# 3_DO.net
KiCad netlist of a schematic drawn in Altium Designer
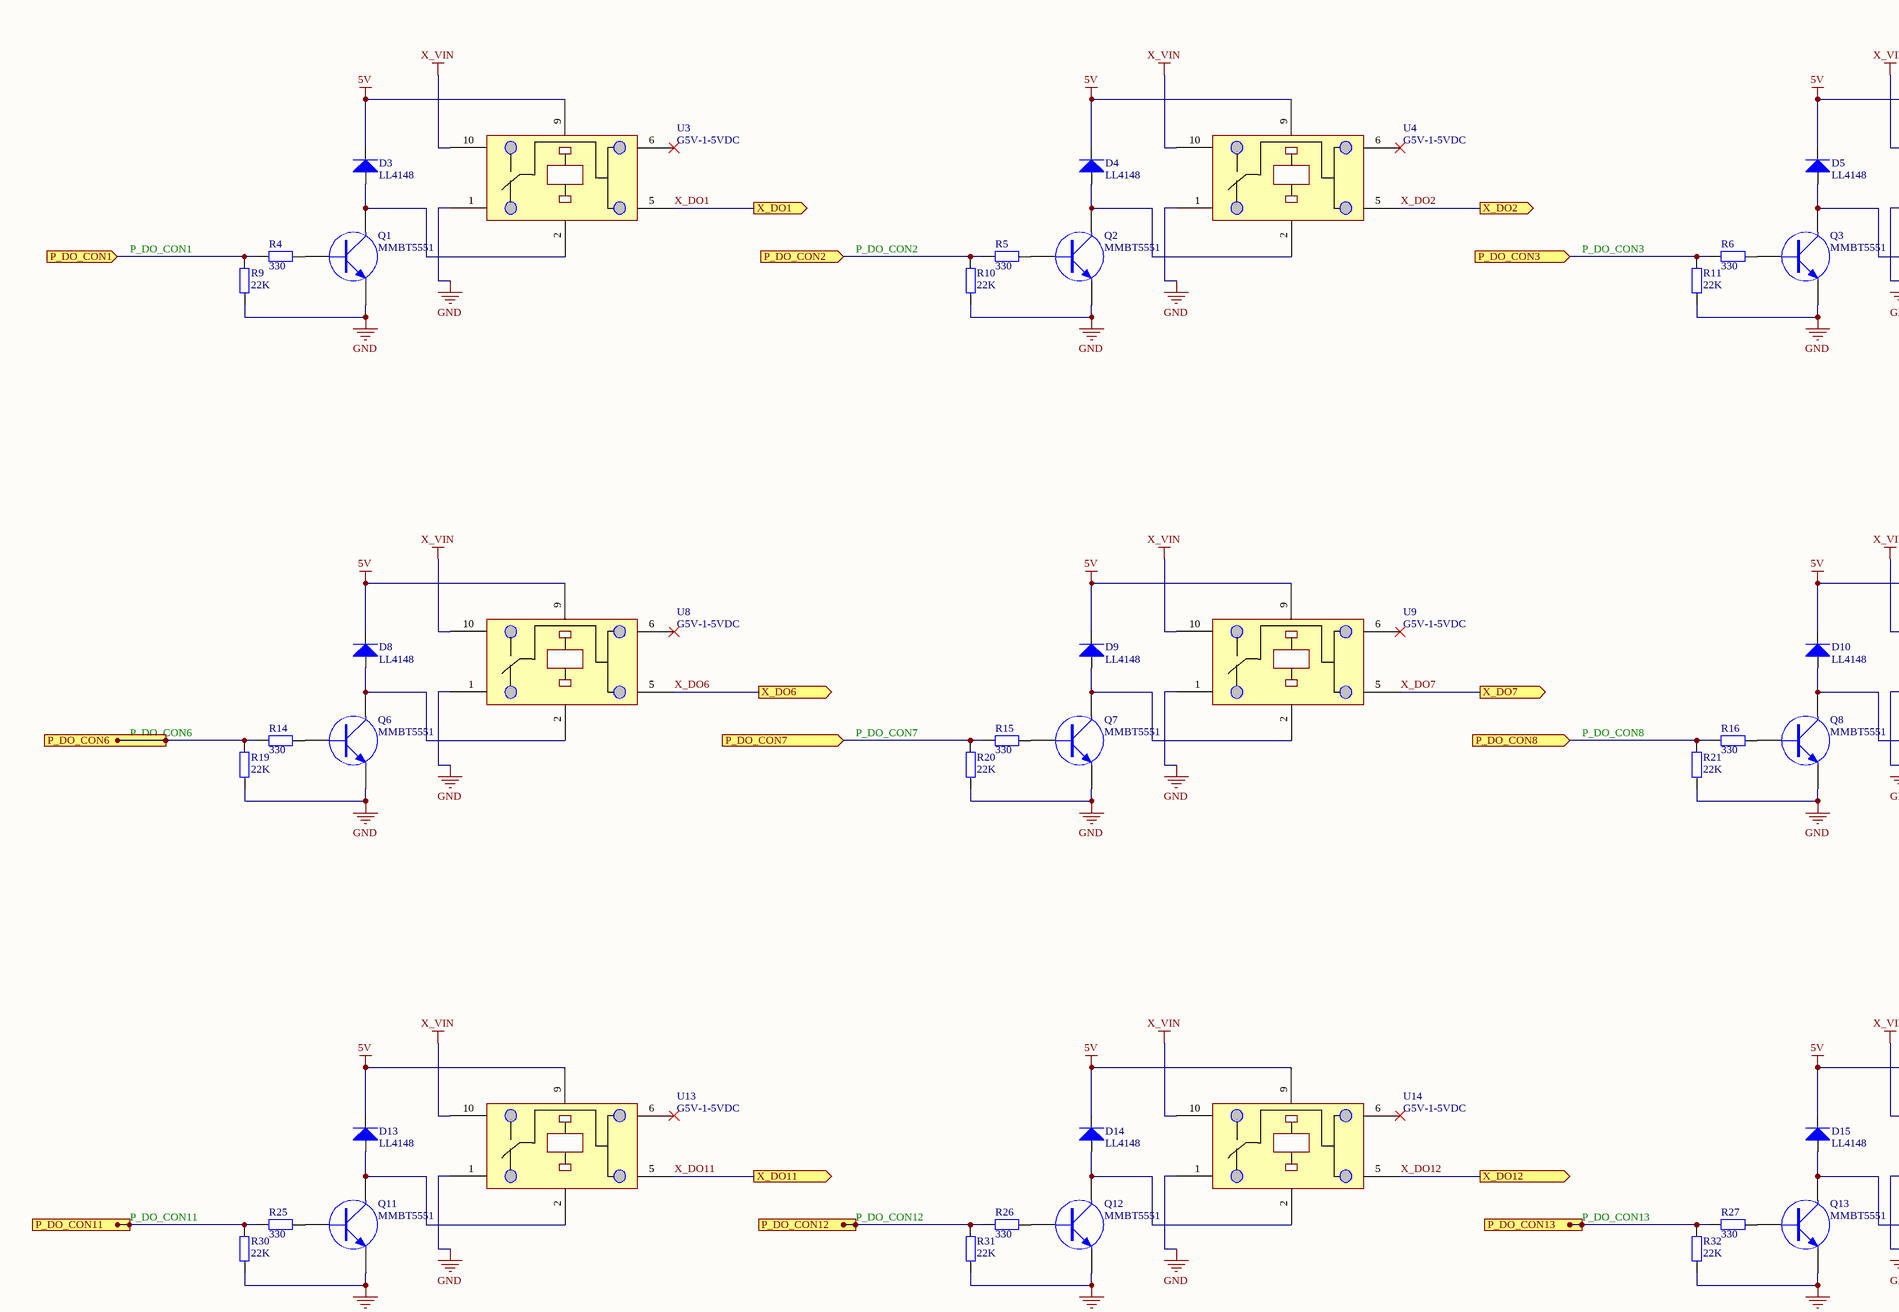
[diagram p0: 3.DO.SchDoc, top left]
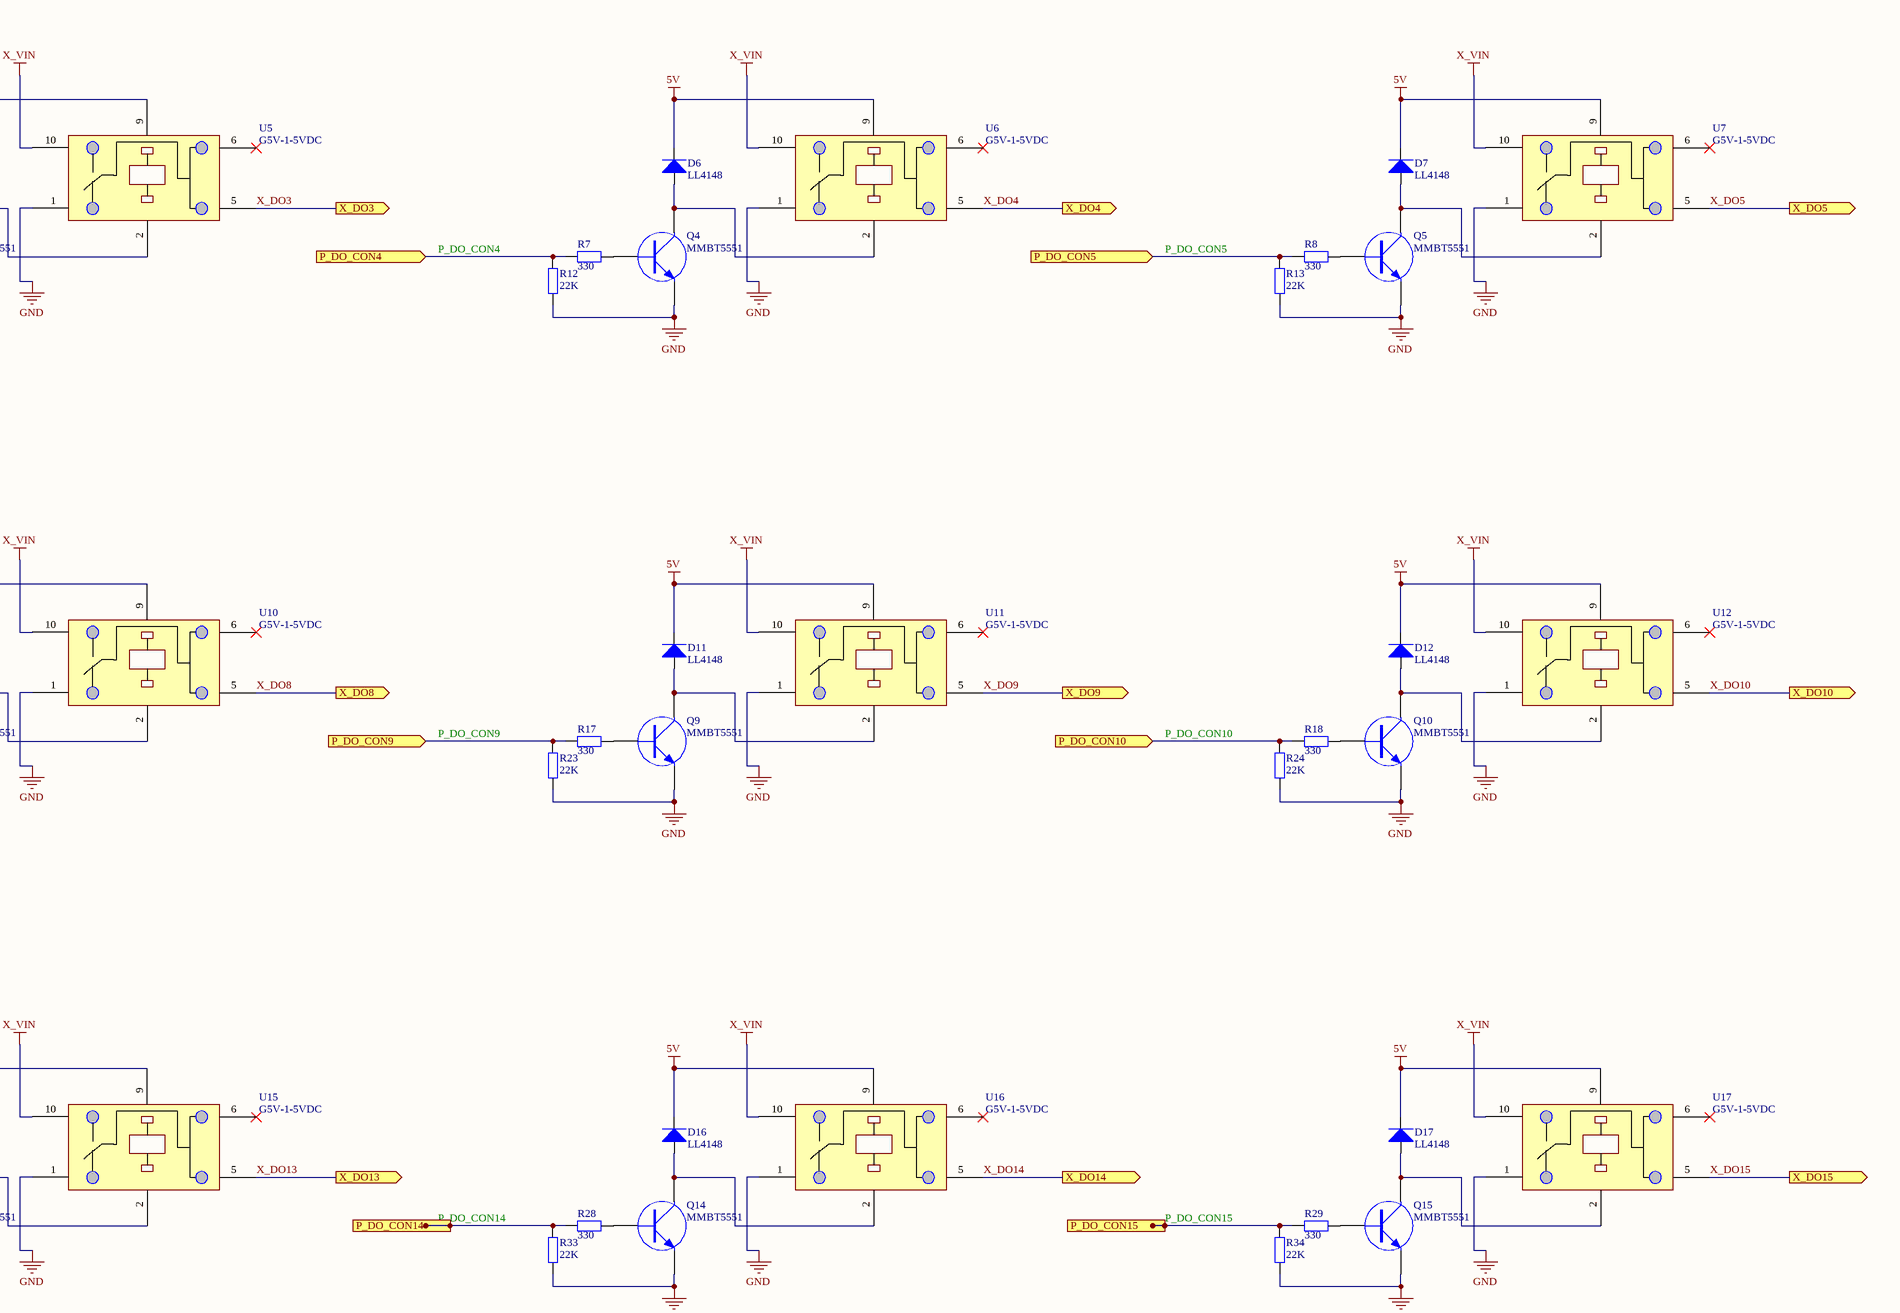
[diagram p1: 3.DO.SchDoc, top right]
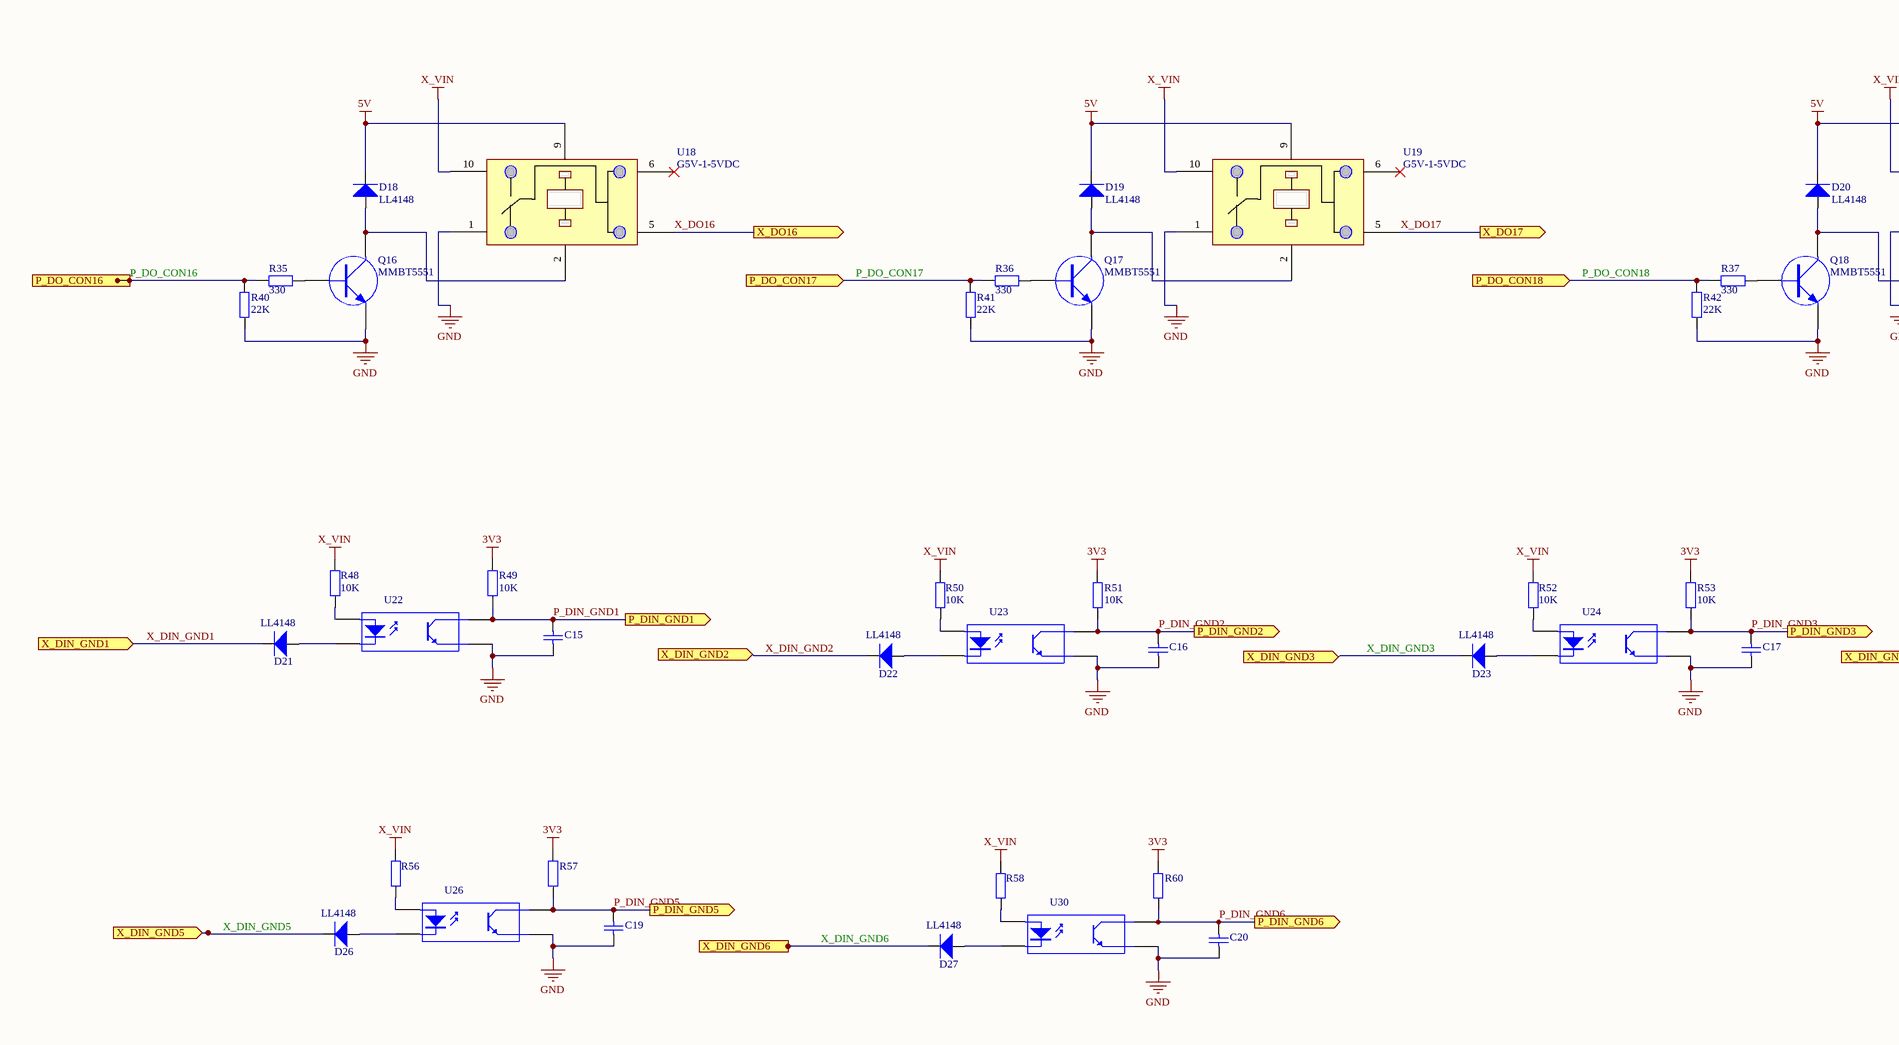
[diagram p2: 3.DO.SchDoc, bottom left]
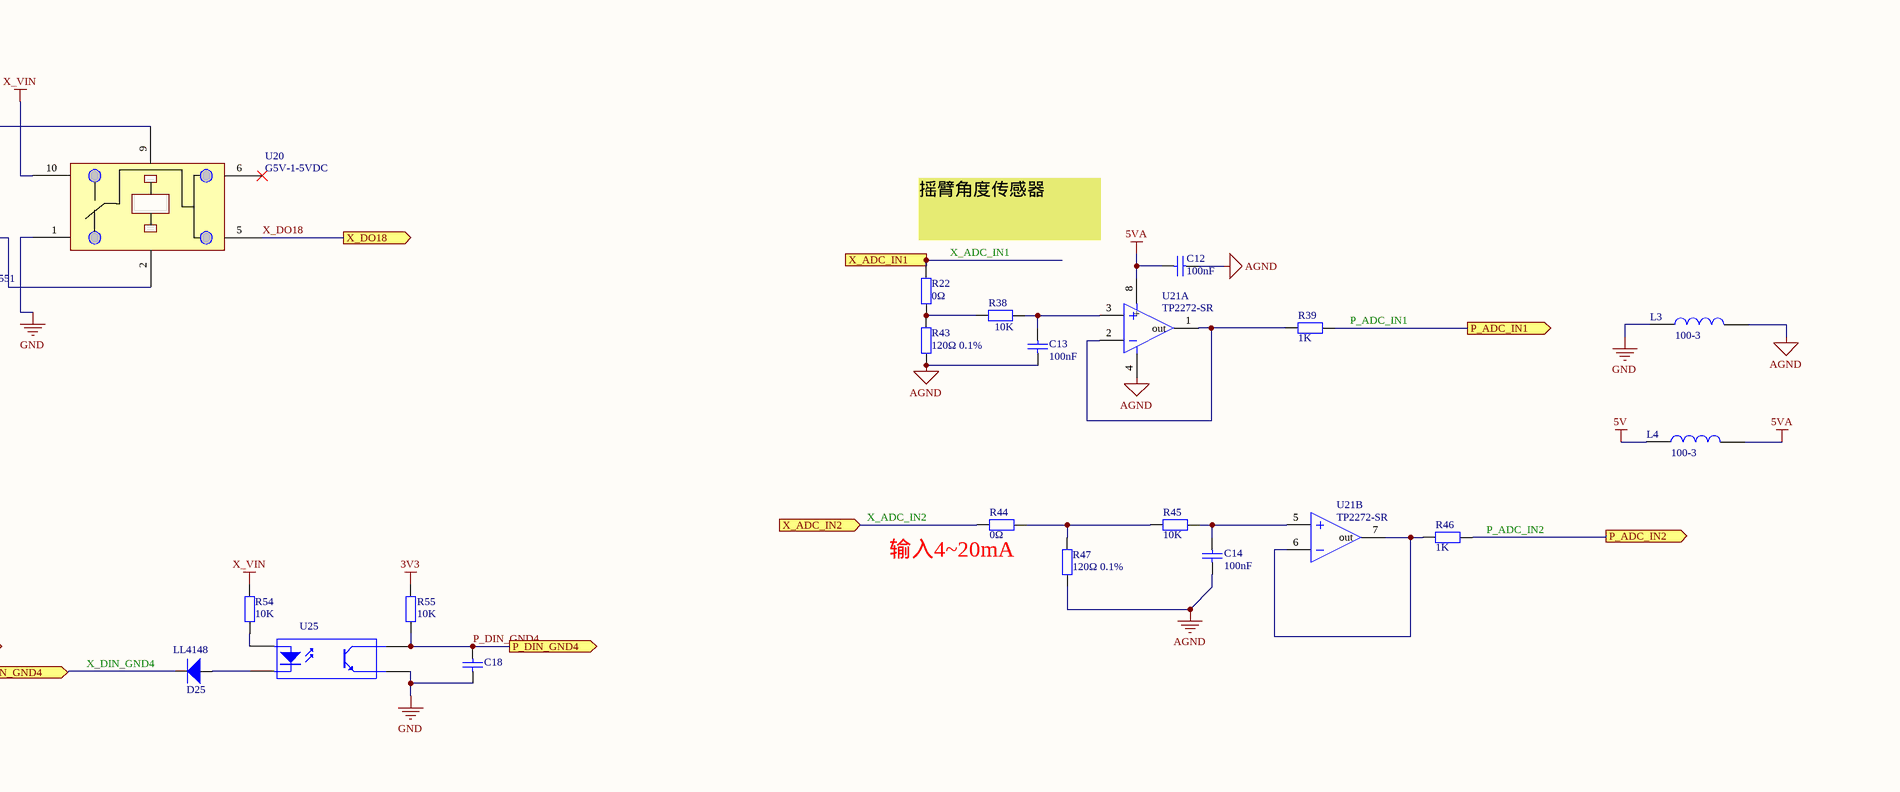
[diagram p3: 3.DO.SchDoc, bottom right]

(export (version "E")
  (design (tool "Eeschema 10.0.6"))
  (components
    (comp (ref "C12")
      (value "100nF")
      (footprint "C0603-M")
      (description "贴片电容/50V100nF/10%")
      (fields (field (name "PUBLISHER") "Altium Limited"))
      (libsource (lib "Miscellaneous Devices") (part "Cap Semi"))
    )
    (comp (ref "C13")
      (value "100nF")
      (footprint "C0603-M")
      (description "贴片电容/50V100nF/10%")
      (fields (field (name "PUBLISHER") "Altium Limited"))
      (libsource (lib "Miscellaneous Devices") (part "Cap Semi"))
    )
    (comp (ref "C14")
      (value "100nF")
      (footprint "C0603-M")
      (description "贴片电容/50V100nF/10%")
      (fields (field (name "PUBLISHER") "Altium Limited"))
      (libsource (lib "Miscellaneous Devices") (part "Cap Semi"))
    )
    (comp (ref "C15")
      (value "10nF")
      (footprint "C0603-M")
      (description "贴片电容")
      (fields (field (name "PUBLISHER") "Altium Limited"))
      (libsource (lib "Miscellaneous Devices") (part "Cap Semi"))
    )
    (comp (ref "C16")
      (value "10nF")
      (footprint "C0603-M")
      (description "贴片电容")
      (fields (field (name "PUBLISHER") "Altium Limited"))
      (libsource (lib "Miscellaneous Devices") (part "Cap Semi"))
    )
    (comp (ref "C17")
      (value "10nF")
      (footprint "C0603-M")
      (description "贴片电容")
      (fields (field (name "PUBLISHER") "Altium Limited"))
      (libsource (lib "Miscellaneous Devices") (part "Cap Semi"))
    )
    (comp (ref "C18")
      (value "10nF")
      (footprint "C0603-M")
      (description "贴片电容")
      (fields (field (name "PUBLISHER") "Altium Limited"))
      (libsource (lib "Miscellaneous Devices") (part "Cap Semi"))
    )
    (comp (ref "C19")
      (value "10nF")
      (footprint "C0603-M")
      (description "贴片电容/50V10nF")
      (fields (field (name "PUBLISHER") "Altium Limited"))
      (libsource (lib "Miscellaneous Devices") (part "Cap Semi"))
    )
    (comp (ref "C20")
      (value "10nF")
      (footprint "C0603-M")
      (description "贴片电容/50V10nF")
      (fields (field (name "PUBLISHER") "Altium Limited"))
      (libsource (lib "Miscellaneous Devices") (part "Cap Semi"))
    )
    (comp (ref "D3")
      (value "LL4148")
      (footprint "LC-LL-34")
      (description "二极管LL4148")
      (libsource (lib "SUPERWDS") (part "DIODE"))
    )
    (comp (ref "D4")
      (value "LL4148")
      (footprint "LC-LL-34")
      (description "二极管LL4148")
      (libsource (lib "SUPERWDS") (part "DIODE"))
    )
    (comp (ref "D5")
      (value "LL4148")
      (footprint "LC-LL-34")
      (description "二极管LL4148")
      (libsource (lib "SUPERWDS") (part "DIODE"))
    )
    (comp (ref "D6")
      (value "LL4148")
      (footprint "LC-LL-34")
      (description "二极管LL4148")
      (libsource (lib "SUPERWDS") (part "DIODE"))
    )
    (comp (ref "D7")
      (value "LL4148")
      (footprint "LC-LL-34")
      (description "二极管LL4148")
      (libsource (lib "SUPERWDS") (part "DIODE"))
    )
    (comp (ref "D8")
      (value "LL4148")
      (footprint "LC-LL-34")
      (description "二极管LL4148")
      (libsource (lib "SUPERWDS") (part "DIODE"))
    )
    (comp (ref "D9")
      (value "LL4148")
      (footprint "LC-LL-34")
      (description "二极管LL4148")
      (libsource (lib "SUPERWDS") (part "DIODE"))
    )
    (comp (ref "D10")
      (value "LL4148")
      (footprint "LC-LL-34")
      (description "二极管LL4148")
      (libsource (lib "SUPERWDS") (part "DIODE"))
    )
    (comp (ref "D11")
      (value "LL4148")
      (footprint "LC-LL-34")
      (description "二极管LL4148")
      (libsource (lib "SUPERWDS") (part "DIODE"))
    )
    (comp (ref "D12")
      (value "LL4148")
      (footprint "LC-LL-34")
      (description "二极管LL4148")
      (libsource (lib "SUPERWDS") (part "DIODE"))
    )
    (comp (ref "D13")
      (value "LL4148")
      (footprint "LC-LL-34")
      (description "二极管LL4148")
      (libsource (lib "SUPERWDS") (part "DIODE"))
    )
    (comp (ref "D14")
      (value "LL4148")
      (footprint "LC-LL-34")
      (description "二极管LL4148")
      (libsource (lib "SUPERWDS") (part "DIODE"))
    )
    (comp (ref "D15")
      (value "LL4148")
      (footprint "LC-LL-34")
      (description "二极管LL4148")
      (libsource (lib "SUPERWDS") (part "DIODE"))
    )
    (comp (ref "D16")
      (value "LL4148")
      (footprint "LC-LL-34")
      (description "二极管LL4148")
      (libsource (lib "SUPERWDS") (part "DIODE"))
    )
    (comp (ref "D17")
      (value "LL4148")
      (footprint "LC-LL-34")
      (description "二极管LL4148")
      (libsource (lib "SUPERWDS") (part "DIODE"))
    )
    (comp (ref "D18")
      (value "LL4148")
      (footprint "LC-LL-34")
      (description "二极管LL4148")
      (libsource (lib "SUPERWDS") (part "DIODE"))
    )
    (comp (ref "D19")
      (value "LL4148")
      (footprint "LC-LL-34")
      (description "二极管LL4148")
      (libsource (lib "SUPERWDS") (part "DIODE"))
    )
    (comp (ref "D20")
      (value "LL4148")
      (footprint "LC-LL-34")
      (description "二极管LL4148")
      (libsource (lib "SUPERWDS") (part "DIODE"))
    )
    (comp (ref "D21")
      (value "LL4148")
      (footprint "LC-LL-34")
      (description "二极管LL4148")
      (libsource (lib "SUPERWDS") (part "DIODE"))
    )
    (comp (ref "D22")
      (value "LL4148")
      (footprint "LC-LL-34")
      (description "二极管LL4148")
      (libsource (lib "SUPERWDS") (part "DIODE"))
    )
    (comp (ref "D23")
      (value "LL4148")
      (footprint "LC-LL-34")
      (description "二极管LL4148")
      (libsource (lib "SUPERWDS") (part "DIODE"))
    )
    (comp (ref "D25")
      (value "LL4148")
      (footprint "LC-LL-34")
      (description "二极管LL4148")
      (libsource (lib "SUPERWDS") (part "DIODE"))
    )
    (comp (ref "D26")
      (value "LL4148")
      (footprint "LC-LL-34")
      (description "二极管LL4148")
      (libsource (lib "SUPERWDS") (part "DIODE"))
    )
    (comp (ref "D27")
      (value "LL4148")
      (footprint "LC-LL-34")
      (description "二极管LL4148")
      (libsource (lib "SUPERWDS") (part "DIODE"))
    )
    (comp (ref "L3")
      (value "100-3")
      (footprint "L0805-M")
      (description "贴片磁珠/100Ω 3A/0805")
      (libsource (lib "*") (part "INDUCTOR"))
    )
    (comp (ref "L4")
      (value "100-3")
      (footprint "L0805-M")
      (description "贴片磁珠/100Ω 3A/0805")
      (libsource (lib "*") (part "INDUCTOR"))
    )
    (comp (ref "Q1")
      (value "MMBT5551")
      (footprint "LC-SOT-23(SOT-23-3)")
      (description "三极管/MMBT5551/NPN")
      (libsource (lib "*") (part "NPN2"))
    )
    (comp (ref "Q2")
      (value "MMBT5551")
      (footprint "LC-SOT-23(SOT-23-3)")
      (description "三极管/MMBT5551/NPN")
      (libsource (lib "*") (part "NPN2"))
    )
    (comp (ref "Q3")
      (value "MMBT5551")
      (footprint "LC-SOT-23(SOT-23-3)")
      (description "三极管/MMBT5551/NPN")
      (libsource (lib "*") (part "NPN2"))
    )
    (comp (ref "Q4")
      (value "MMBT5551")
      (footprint "LC-SOT-23(SOT-23-3)")
      (description "三极管/MMBT5551/NPN")
      (libsource (lib "*") (part "NPN2"))
    )
    (comp (ref "Q5")
      (value "MMBT5551")
      (footprint "LC-SOT-23(SOT-23-3)")
      (description "三极管/MMBT5551/NPN")
      (libsource (lib "*") (part "NPN2"))
    )
    (comp (ref "Q6")
      (value "MMBT5551")
      (footprint "LC-SOT-23(SOT-23-3)")
      (description "三极管/MMBT5551/NPN")
      (libsource (lib "*") (part "NPN2"))
    )
    (comp (ref "Q7")
      (value "MMBT5551")
      (footprint "LC-SOT-23(SOT-23-3)")
      (description "三极管/MMBT5551/NPN")
      (libsource (lib "*") (part "NPN2"))
    )
    (comp (ref "Q8")
      (value "MMBT5551")
      (footprint "LC-SOT-23(SOT-23-3)")
      (description "三极管/MMBT5551/NPN")
      (libsource (lib "*") (part "NPN2"))
    )
    (comp (ref "Q9")
      (value "MMBT5551")
      (footprint "LC-SOT-23(SOT-23-3)")
      (description "三极管/MMBT5551/NPN")
      (libsource (lib "*") (part "NPN2"))
    )
    (comp (ref "Q10")
      (value "MMBT5551")
      (footprint "LC-SOT-23(SOT-23-3)")
      (description "三极管/MMBT5551/NPN")
      (libsource (lib "*") (part "NPN2"))
    )
    (comp (ref "Q11")
      (value "MMBT5551")
      (footprint "LC-SOT-23(SOT-23-3)")
      (description "三极管/MMBT5551/NPN")
      (libsource (lib "*") (part "NPN2"))
    )
    (comp (ref "Q12")
      (value "MMBT5551")
      (footprint "LC-SOT-23(SOT-23-3)")
      (description "三极管/MMBT5551/NPN")
      (libsource (lib "*") (part "NPN2"))
    )
    (comp (ref "Q13")
      (value "MMBT5551")
      (footprint "LC-SOT-23(SOT-23-3)")
      (description "三极管/MMBT5551/NPN")
      (libsource (lib "*") (part "NPN2"))
    )
    (comp (ref "Q14")
      (value "MMBT5551")
      (footprint "LC-SOT-23(SOT-23-3)")
      (description "三极管/MMBT5551/NPN")
      (libsource (lib "*") (part "NPN2"))
    )
    (comp (ref "Q15")
      (value "MMBT5551")
      (footprint "LC-SOT-23(SOT-23-3)")
      (description "三极管/MMBT5551/NPN")
      (libsource (lib "*") (part "NPN2"))
    )
    (comp (ref "Q16")
      (value "MMBT5551")
      (footprint "LC-SOT-23(SOT-23-3)")
      (description "三极管/MMBT5551/NPN")
      (libsource (lib "*") (part "NPN2"))
    )
    (comp (ref "Q17")
      (value "MMBT5551")
      (footprint "LC-SOT-23(SOT-23-3)")
      (description "三极管/MMBT5551/NPN")
      (libsource (lib "*") (part "NPN2"))
    )
    (comp (ref "Q18")
      (value "MMBT5551")
      (footprint "LC-SOT-23(SOT-23-3)")
      (description "三极管/MMBT5551/NPN")
      (libsource (lib "*") (part "NPN2"))
    )
    (comp (ref "R4")
      (value "330")
      (footprint "R0603-M")
      (description "贴片电阻/330")
      (fields (field (name "PUBLISHER") "Altium Limited"))
      (libsource (lib "") (part "Res2_1"))
    )
    (comp (ref "R5")
      (value "330")
      (footprint "R0603-M")
      (description "贴片电阻/330")
      (fields (field (name "PUBLISHER") "Altium Limited"))
      (libsource (lib "") (part "Res2_1"))
    )
    (comp (ref "R6")
      (value "330")
      (footprint "R0603-M")
      (description "贴片电阻/330")
      (fields (field (name "PUBLISHER") "Altium Limited"))
      (libsource (lib "") (part "Res2_1"))
    )
    (comp (ref "R7")
      (value "330")
      (footprint "R0603-M")
      (description "贴片电阻/330")
      (fields (field (name "PUBLISHER") "Altium Limited"))
      (libsource (lib "") (part "Res2_1"))
    )
    (comp (ref "R8")
      (value "330")
      (footprint "R0603-M")
      (description "贴片电阻/330")
      (fields (field (name "PUBLISHER") "Altium Limited"))
      (libsource (lib "") (part "Res2_1"))
    )
    (comp (ref "R9")
      (value "22K")
      (footprint "R0603-M")
      (description "贴片电阻")
      (fields (field (name "PUBLISHER") "Altium Limited"))
      (libsource (lib "Miscellaneous Devices") (part "Res2"))
    )
    (comp (ref "R10")
      (value "22K")
      (footprint "R0603-M")
      (description "贴片电阻")
      (fields (field (name "PUBLISHER") "Altium Limited"))
      (libsource (lib "Miscellaneous Devices") (part "Res2"))
    )
    (comp (ref "R11")
      (value "22K")
      (footprint "R0603-M")
      (description "贴片电阻")
      (fields (field (name "PUBLISHER") "Altium Limited"))
      (libsource (lib "Miscellaneous Devices") (part "Res2"))
    )
    (comp (ref "R12")
      (value "22K")
      (footprint "R0603-M")
      (description "贴片电阻")
      (fields (field (name "PUBLISHER") "Altium Limited"))
      (libsource (lib "Miscellaneous Devices") (part "Res2"))
    )
    (comp (ref "R13")
      (value "22K")
      (footprint "R0603-M")
      (description "贴片电阻")
      (fields (field (name "PUBLISHER") "Altium Limited"))
      (libsource (lib "Miscellaneous Devices") (part "Res2"))
    )
    (comp (ref "R14")
      (value "330")
      (footprint "R0603-M")
      (description "贴片电阻/330")
      (fields (field (name "PUBLISHER") "Altium Limited"))
      (libsource (lib "") (part "Res2_1"))
    )
    (comp (ref "R15")
      (value "330")
      (footprint "R0603-M")
      (description "贴片电阻/330")
      (fields (field (name "PUBLISHER") "Altium Limited"))
      (libsource (lib "") (part "Res2_1"))
    )
    (comp (ref "R16")
      (value "330")
      (footprint "R0603-M")
      (description "贴片电阻/330")
      (fields (field (name "PUBLISHER") "Altium Limited"))
      (libsource (lib "") (part "Res2_1"))
    )
    (comp (ref "R17")
      (value "330")
      (footprint "R0603-M")
      (description "贴片电阻/330")
      (fields (field (name "PUBLISHER") "Altium Limited"))
      (libsource (lib "") (part "Res2_1"))
    )
    (comp (ref "R18")
      (value "330")
      (footprint "R0603-M")
      (description "贴片电阻/330")
      (fields (field (name "PUBLISHER") "Altium Limited"))
      (libsource (lib "") (part "Res2_1"))
    )
    (comp (ref "R19")
      (value "22K")
      (footprint "R0603-M")
      (description "贴片电阻")
      (fields (field (name "PUBLISHER") "Altium Limited"))
      (libsource (lib "Miscellaneous Devices") (part "Res2"))
    )
    (comp (ref "R20")
      (value "22K")
      (footprint "R0603-M")
      (description "贴片电阻")
      (fields (field (name "PUBLISHER") "Altium Limited"))
      (libsource (lib "Miscellaneous Devices") (part "Res2"))
    )
    (comp (ref "R21")
      (value "22K")
      (footprint "R0603-M")
      (description "贴片电阻")
      (fields (field (name "PUBLISHER") "Altium Limited"))
      (libsource (lib "Miscellaneous Devices") (part "Res2"))
    )
    (comp (ref "R22")
      (value "0Ω")
      (footprint "R0603-M")
      (fields (field (name "PUBLISHER") "Altium Limited"))
      (libsource (lib "SUPERWDS") (part "RES2"))
    )
    (comp (ref "R23")
      (value "22K")
      (footprint "R0603-M")
      (description "贴片电阻")
      (fields (field (name "PUBLISHER") "Altium Limited"))
      (libsource (lib "Miscellaneous Devices") (part "Res2"))
    )
    (comp (ref "R24")
      (value "22K")
      (footprint "R0603-M")
      (description "贴片电阻")
      (fields (field (name "PUBLISHER") "Altium Limited"))
      (libsource (lib "Miscellaneous Devices") (part "Res2"))
    )
    (comp (ref "R25")
      (value "330")
      (footprint "R0603-M")
      (description "贴片电阻/330")
      (fields (field (name "PUBLISHER") "Altium Limited"))
      (libsource (lib "") (part "Res2_1"))
    )
    (comp (ref "R26")
      (value "330")
      (footprint "R0603-M")
      (description "贴片电阻/330")
      (fields (field (name "PUBLISHER") "Altium Limited"))
      (libsource (lib "") (part "Res2_1"))
    )
    (comp (ref "R27")
      (value "330")
      (footprint "R0603-M")
      (description "贴片电阻/330")
      (fields (field (name "PUBLISHER") "Altium Limited"))
      (libsource (lib "") (part "Res2_1"))
    )
    (comp (ref "R28")
      (value "330")
      (footprint "R0603-M")
      (description "贴片电阻/330")
      (fields (field (name "PUBLISHER") "Altium Limited"))
      (libsource (lib "") (part "Res2_1"))
    )
    (comp (ref "R29")
      (value "330")
      (footprint "R0603-M")
      (description "贴片电阻/330")
      (fields (field (name "PUBLISHER") "Altium Limited"))
      (libsource (lib "") (part "Res2_1"))
    )
    (comp (ref "R30")
      (value "22K")
      (footprint "R0603-M")
      (description "贴片电阻")
      (fields (field (name "PUBLISHER") "Altium Limited"))
      (libsource (lib "Miscellaneous Devices") (part "Res2"))
    )
    (comp (ref "R31")
      (value "22K")
      (footprint "R0603-M")
      (description "贴片电阻")
      (fields (field (name "PUBLISHER") "Altium Limited"))
      (libsource (lib "Miscellaneous Devices") (part "Res2"))
    )
    (comp (ref "R32")
      (value "22K")
      (footprint "R0603-M")
      (description "贴片电阻")
      (fields (field (name "PUBLISHER") "Altium Limited"))
      (libsource (lib "Miscellaneous Devices") (part "Res2"))
    )
    (comp (ref "R33")
      (value "22K")
      (footprint "R0603-M")
      (description "贴片电阻")
      (fields (field (name "PUBLISHER") "Altium Limited"))
      (libsource (lib "Miscellaneous Devices") (part "Res2"))
    )
    (comp (ref "R34")
      (value "22K")
      (footprint "R0603-M")
      (description "贴片电阻")
      (fields (field (name "PUBLISHER") "Altium Limited"))
      (libsource (lib "Miscellaneous Devices") (part "Res2"))
    )
    (comp (ref "R35")
      (value "330")
      (footprint "R0603-M")
      (description "贴片电阻/330")
      (fields (field (name "PUBLISHER") "Altium Limited"))
      (libsource (lib "") (part "Res2_1"))
    )
    (comp (ref "R36")
      (value "330")
      (footprint "R0603-M")
      (description "贴片电阻/330")
      (fields (field (name "PUBLISHER") "Altium Limited"))
      (libsource (lib "") (part "Res2_1"))
    )
    (comp (ref "R37")
      (value "330")
      (footprint "R0603-M")
      (description "贴片电阻/330")
      (fields (field (name "PUBLISHER") "Altium Limited"))
      (libsource (lib "") (part "Res2_1"))
    )
    (comp (ref "R38")
      (value "10K")
      (footprint "R0603-M")
      (description "贴片电阻/10K1%")
      (fields (field (name "PUBLISHER") "Altium Limited"))
      (libsource (lib "SUPERWDS") (part "Res2"))
    )
    (comp (ref "R39")
      (value "1K")
      (footprint "R0603-M")
      (description "贴片电阻")
      (fields (field (name "PUBLISHER") "Altium Limited"))
      (libsource (lib "") (part "Res2_1"))
    )
    (comp (ref "R40")
      (value "22K")
      (footprint "R0603-M")
      (description "贴片电阻")
      (fields (field (name "PUBLISHER") "Altium Limited"))
      (libsource (lib "Miscellaneous Devices") (part "Res2"))
    )
    (comp (ref "R41")
      (value "22K")
      (footprint "R0603-M")
      (description "贴片电阻")
      (fields (field (name "PUBLISHER") "Altium Limited"))
      (libsource (lib "Miscellaneous Devices") (part "Res2"))
    )
    (comp (ref "R42")
      (value "22K")
      (footprint "R0603-M")
      (description "贴片电阻")
      (fields (field (name "PUBLISHER") "Altium Limited"))
      (libsource (lib "Miscellaneous Devices") (part "Res2"))
    )
    (comp (ref "R43")
      (value "120Ω 0.1%")
      (footprint "R0603-M")
      (description "贴片电阻")
      (fields (field (name "PUBLISHER") "Altium Limited"))
      (libsource (lib "Miscellaneous Devices") (part "Res2"))
    )
    (comp (ref "R44")
      (value "0Ω")
      (footprint "R0603-M")
      (fields (field (name "PUBLISHER") "Altium Limited"))
      (libsource (lib "") (part "RES2_1"))
    )
    (comp (ref "R45")
      (value "10K")
      (footprint "R0603-M")
      (description "贴片电阻/10K1%")
      (fields (field (name "PUBLISHER") "Altium Limited"))
      (libsource (lib "") (part "Res2_1"))
    )
    (comp (ref "R46")
      (value "1K")
      (footprint "R0603-M")
      (description "贴片电阻/1K")
      (fields (field (name "PUBLISHER") "Altium Limited"))
      (libsource (lib "") (part "Res2_1"))
    )
    (comp (ref "R47")
      (value "120Ω 0.1%")
      (footprint "R0603-M")
      (description "贴片高精密、低温漂电阻//100Ω0.1%")
      (fields (field (name "PUBLISHER") "Altium Limited"))
      (libsource (lib "") (part "Res2_2"))
    )
    (comp (ref "R48")
      (value "10K")
      (footprint "R0603-M")
      (description "贴片电阻")
      (fields (field (name "PUBLISHER") "Altium Limited"))
      (libsource (lib "") (part "Res2_2"))
    )
    (comp (ref "R49")
      (value "10K")
      (footprint "R0603-M")
      (description "贴片电阻")
      (fields (field (name "PUBLISHER") "Altium Limited"))
      (libsource (lib "Miscellaneous Devices") (part "Res2"))
    )
    (comp (ref "R50")
      (value "10K")
      (footprint "R0603-M")
      (description "贴片电阻")
      (fields (field (name "PUBLISHER") "Altium Limited"))
      (libsource (lib "") (part "Res2_2"))
    )
    (comp (ref "R51")
      (value "10K")
      (footprint "R0603-M")
      (description "贴片电阻")
      (fields (field (name "PUBLISHER") "Altium Limited"))
      (libsource (lib "Miscellaneous Devices") (part "Res2"))
    )
    (comp (ref "R52")
      (value "10K")
      (footprint "R0603-M")
      (description "贴片电阻")
      (fields (field (name "PUBLISHER") "Altium Limited"))
      (libsource (lib "") (part "Res2_2"))
    )
    (comp (ref "R53")
      (value "10K")
      (footprint "R0603-M")
      (description "贴片电阻")
      (fields (field (name "PUBLISHER") "Altium Limited"))
      (libsource (lib "Miscellaneous Devices") (part "Res2"))
    )
    (comp (ref "R54")
      (value "10K")
      (footprint "R0603-M")
      (description "贴片电阻")
      (fields (field (name "PUBLISHER") "Altium Limited"))
      (libsource (lib "") (part "Res2_2"))
    )
    (comp (ref "R55")
      (value "10K")
      (footprint "R0603-M")
      (description "贴片电阻")
      (fields (field (name "PUBLISHER") "Altium Limited"))
      (libsource (lib "Miscellaneous Devices") (part "Res2"))
    )
    (comp (ref "R56")
      (value "10K")
      (footprint "R0603-M")
      (description "贴片电阻/10K")
      (fields (field (name "PUBLISHER") "Altium Limited"))
      (libsource (lib "") (part "Res2_2"))
    )
    (comp (ref "R57")
      (value "10K")
      (footprint "R0603-M")
      (description "贴片电阻/10K")
      (fields (field (name "PUBLISHER") "Altium Limited"))
      (libsource (lib "Miscellaneous Devices") (part "Res2"))
    )
    (comp (ref "R58")
      (value "10K")
      (footprint "R0603-M")
      (description "贴片电阻/10K")
      (fields (field (name "PUBLISHER") "Altium Limited"))
      (libsource (lib "") (part "Res2_2"))
    )
    (comp (ref "R60")
      (value "10K")
      (footprint "R0603-M")
      (description "贴片电阻/10K")
      (fields (field (name "PUBLISHER") "Altium Limited"))
      (libsource (lib "Miscellaneous Devices") (part "Res2"))
    )
    (comp (ref "U3")
      (value "G5V-1-5VDC")
      (footprint "G5V-1")
      (description "继电器//欧姆龙//G5V-1-5VDC")
      (libsource (lib "SIC_CtrLBoard_") (part "G5V-1"))
    )
    (comp (ref "U4")
      (value "G5V-1-5VDC")
      (footprint "G5V-1")
      (description "继电器//欧姆龙//G5V-1-5VDC")
      (libsource (lib "SIC_CtrLBoard_") (part "G5V-1"))
    )
    (comp (ref "U5")
      (value "G5V-1-5VDC")
      (footprint "G5V-1")
      (description "继电器//欧姆龙//G5V-1-5VDC")
      (libsource (lib "SIC_CtrLBoard_") (part "G5V-1"))
    )
    (comp (ref "U6")
      (value "G5V-1-5VDC")
      (footprint "G5V-1")
      (description "继电器//欧姆龙//G5V-1-5VDC")
      (libsource (lib "SIC_CtrLBoard_") (part "G5V-1"))
    )
    (comp (ref "U7")
      (value "G5V-1-5VDC")
      (footprint "G5V-1")
      (description "继电器//欧姆龙//G5V-1-5VDC")
      (libsource (lib "SIC_CtrLBoard_") (part "G5V-1"))
    )
    (comp (ref "U8")
      (value "G5V-1-5VDC")
      (footprint "G5V-1")
      (description "继电器//欧姆龙//G5V-1-5VDC")
      (libsource (lib "SIC_CtrLBoard_") (part "G5V-1"))
    )
    (comp (ref "U9")
      (value "G5V-1-5VDC")
      (footprint "G5V-1")
      (description "继电器//欧姆龙//G5V-1-5VDC")
      (libsource (lib "SIC_CtrLBoard_") (part "G5V-1"))
    )
    (comp (ref "U10")
      (value "G5V-1-5VDC")
      (footprint "G5V-1")
      (description "继电器//欧姆龙//G5V-1-5VDC")
      (libsource (lib "SIC_CtrLBoard_") (part "G5V-1"))
    )
    (comp (ref "U11")
      (value "G5V-1-5VDC")
      (footprint "G5V-1")
      (description "继电器//欧姆龙//G5V-1-5VDC")
      (libsource (lib "SIC_CtrLBoard_") (part "G5V-1"))
    )
    (comp (ref "U12")
      (value "G5V-1-5VDC")
      (footprint "G5V-1")
      (description "继电器//欧姆龙//G5V-1-5VDC")
      (libsource (lib "SIC_CtrLBoard_") (part "G5V-1"))
    )
    (comp (ref "U13")
      (value "G5V-1-5VDC")
      (footprint "G5V-1")
      (description "继电器//欧姆龙//G5V-1-5VDC")
      (libsource (lib "SIC_CtrLBoard_") (part "G5V-1"))
    )
    (comp (ref "U14")
      (value "G5V-1-5VDC")
      (footprint "G5V-1")
      (description "继电器//欧姆龙//G5V-1-5VDC")
      (libsource (lib "SIC_CtrLBoard_") (part "G5V-1"))
    )
    (comp (ref "U15")
      (value "G5V-1-5VDC")
      (footprint "G5V-1")
      (description "继电器//欧姆龙//G5V-1-5VDC")
      (libsource (lib "SIC_CtrLBoard_") (part "G5V-1"))
    )
    (comp (ref "U16")
      (value "G5V-1-5VDC")
      (footprint "G5V-1")
      (description "继电器//欧姆龙//G5V-1-5VDC")
      (libsource (lib "SIC_CtrLBoard_") (part "G5V-1"))
    )
    (comp (ref "U17")
      (value "G5V-1-5VDC")
      (footprint "G5V-1")
      (description "继电器//欧姆龙//G5V-1-5VDC")
      (libsource (lib "SIC_CtrLBoard_") (part "G5V-1"))
    )
    (comp (ref "U18")
      (value "G5V-1-5VDC")
      (footprint "G5V-1")
      (description "继电器//欧姆龙//G5V-1-5VDC")
      (libsource (lib "SIC_CtrLBoard_") (part "G5V-1"))
    )
    (comp (ref "U19")
      (value "G5V-1-5VDC")
      (footprint "G5V-1")
      (description "继电器//欧姆龙//G5V-1-5VDC")
      (libsource (lib "SIC_CtrLBoard_") (part "G5V-1"))
    )
    (comp (ref "U20")
      (value "G5V-1-5VDC")
      (footprint "G5V-1")
      (description "继电器//欧姆龙//G5V-1-5VDC")
      (libsource (lib "SIC_CtrLBoard_") (part "G5V-1"))
    )
    (comp (ref "U21")
      (value "TP2272-SR")
      (footprint "SOIC-127P-8N")
      (libsource (lib "SUPERWDS") (part "LM358"))
    )
    (comp (ref "U22")
      (value "EL357N(B)(TA)-G")
      (footprint "LC-SOP-4_P2.54")
      (description "贴片光耦//EL357N(B)(TA)-G")
      (libsource (lib "SUPERWDS") (part "EL357N(B)(TA)-G"))
    )
    (comp (ref "U23")
      (value "EL357N(B)(TA)-G")
      (footprint "LC-SOP-4_P2.54")
      (description "贴片光耦//EL357N(B)(TA)-G")
      (libsource (lib "SUPERWDS") (part "EL357N(B)(TA)-G"))
    )
    (comp (ref "U24")
      (value "EL357N(B)(TA)-G")
      (footprint "LC-SOP-4_P2.54")
      (description "贴片光耦//EL357N(B)(TA)-G")
      (libsource (lib "SUPERWDS") (part "EL357N(B)(TA)-G"))
    )
    (comp (ref "U25")
      (value "EL357N(B)(TA)-G")
      (footprint "LC-SOP-4_P2.54")
      (description "贴片光耦//EL357N(B)(TA)-G")
      (libsource (lib "SUPERWDS") (part "EL357N(B)(TA)-G"))
    )
    (comp (ref "U26")
      (value "EL357N(B)(TA)-G")
      (footprint "LC-SOP-4_P2.54")
      (description "贴片光耦//EL357N(B)(TA)-G")
      (libsource (lib "SUPERWDS") (part "EL357N(B)(TA)-G"))
    )
    (comp (ref "U30")
      (value "EL357N(B)(TA)-G")
      (footprint "LC-SOP-4_P2.54")
      (description "贴片光耦//EL357N(B)(TA)-G")
      (libsource (lib "SUPERWDS") (part "EL357N(B)(TA)-G"))
    )
  )
  (nets
    (net (code "1") (name "/P_ADC_IN1") (class "Default")
      (node (ref "R39") (pin "1") (pinfunction "1_1") (pintype "passive"))
    )
    (net (code "2") (name "/P_ADC_IN2") (class "Default")
      (node (ref "R46") (pin "1") (pinfunction "1_1") (pintype "passive"))
    )
    (net (code "3") (name "/P_DIN_GND1") (class "Default")
      (node (ref "C15") (pin "1") (pinfunction "1_1") (pintype "passive"))
      (node (ref "R49") (pin "1") (pinfunction "1_1") (pintype "passive"))
      (node (ref "U22") (pin "4") (pinfunction "C_4") (pintype "passive"))
    )
    (net (code "4") (name "/P_DIN_GND2") (class "Default")
      (node (ref "C16") (pin "1") (pinfunction "1_1") (pintype "passive"))
      (node (ref "R51") (pin "1") (pinfunction "1_1") (pintype "passive"))
      (node (ref "U23") (pin "4") (pinfunction "C_4") (pintype "passive"))
    )
    (net (code "5") (name "/P_DIN_GND3") (class "Default")
      (node (ref "C17") (pin "1") (pinfunction "1_1") (pintype "passive"))
      (node (ref "R53") (pin "1") (pinfunction "1_1") (pintype "passive"))
      (node (ref "U24") (pin "4") (pinfunction "C_4") (pintype "passive"))
    )
    (net (code "6") (name "/P_DIN_GND4") (class "Default")
      (node (ref "C18") (pin "1") (pinfunction "1_1") (pintype "passive"))
      (node (ref "R55") (pin "1") (pinfunction "1_1") (pintype "passive"))
      (node (ref "U25") (pin "4") (pinfunction "C_4") (pintype "passive"))
    )
    (net (code "7") (name "/P_DIN_GND5") (class "Default")
      (node (ref "C19") (pin "1") (pinfunction "1_1") (pintype "passive"))
      (node (ref "R57") (pin "1") (pinfunction "1_1") (pintype "passive"))
      (node (ref "U26") (pin "4") (pinfunction "C_4") (pintype "passive"))
    )
    (net (code "8") (name "/P_DIN_GND6") (class "Default")
      (node (ref "C20") (pin "1") (pinfunction "1_1") (pintype "passive"))
      (node (ref "R60") (pin "1") (pinfunction "1_1") (pintype "passive"))
      (node (ref "U30") (pin "4") (pinfunction "C_4") (pintype "passive"))
    )
    (net (code "9") (name "/P_DO_CON1") (class "Default")
      (node (ref "R4") (pin "2") (pinfunction "2_2") (pintype "passive"))
      (node (ref "R9") (pin "2") (pinfunction "2_2") (pintype "passive"))
    )
    (net (code "10") (name "/P_DO_CON2") (class "Default")
      (node (ref "R10") (pin "2") (pinfunction "2_2") (pintype "passive"))
      (node (ref "R5") (pin "2") (pinfunction "2_2") (pintype "passive"))
    )
    (net (code "11") (name "/P_DO_CON3") (class "Default")
      (node (ref "R11") (pin "2") (pinfunction "2_2") (pintype "passive"))
      (node (ref "R6") (pin "2") (pinfunction "2_2") (pintype "passive"))
    )
    (net (code "12") (name "/P_DO_CON4") (class "Default")
      (node (ref "R12") (pin "2") (pinfunction "2_2") (pintype "passive"))
      (node (ref "R7") (pin "2") (pinfunction "2_2") (pintype "passive"))
    )
    (net (code "13") (name "/P_DO_CON5") (class "Default")
      (node (ref "R13") (pin "2") (pinfunction "2_2") (pintype "passive"))
      (node (ref "R8") (pin "2") (pinfunction "2_2") (pintype "passive"))
    )
    (net (code "14") (name "/P_DO_CON6") (class "Default")
      (node (ref "R14") (pin "2") (pinfunction "2_2") (pintype "passive"))
      (node (ref "R19") (pin "2") (pinfunction "2_2") (pintype "passive"))
    )
    (net (code "15") (name "/P_DO_CON7") (class "Default")
      (node (ref "R15") (pin "2") (pinfunction "2_2") (pintype "passive"))
      (node (ref "R20") (pin "2") (pinfunction "2_2") (pintype "passive"))
    )
    (net (code "16") (name "/P_DO_CON8") (class "Default")
      (node (ref "R16") (pin "2") (pinfunction "2_2") (pintype "passive"))
      (node (ref "R21") (pin "2") (pinfunction "2_2") (pintype "passive"))
    )
    (net (code "17") (name "/P_DO_CON9") (class "Default")
      (node (ref "R17") (pin "2") (pinfunction "2_2") (pintype "passive"))
      (node (ref "R23") (pin "2") (pinfunction "2_2") (pintype "passive"))
    )
    (net (code "18") (name "/P_DO_CON10") (class "Default")
      (node (ref "R18") (pin "2") (pinfunction "2_2") (pintype "passive"))
      (node (ref "R24") (pin "2") (pinfunction "2_2") (pintype "passive"))
    )
    (net (code "19") (name "/P_DO_CON11") (class "Default")
      (node (ref "R25") (pin "2") (pinfunction "2_2") (pintype "passive"))
      (node (ref "R30") (pin "2") (pinfunction "2_2") (pintype "passive"))
    )
    (net (code "20") (name "/P_DO_CON12") (class "Default")
      (node (ref "R26") (pin "2") (pinfunction "2_2") (pintype "passive"))
      (node (ref "R31") (pin "2") (pinfunction "2_2") (pintype "passive"))
    )
    (net (code "21") (name "/P_DO_CON13") (class "Default")
      (node (ref "R27") (pin "2") (pinfunction "2_2") (pintype "passive"))
      (node (ref "R32") (pin "2") (pinfunction "2_2") (pintype "passive"))
    )
    (net (code "22") (name "/P_DO_CON14") (class "Default")
      (node (ref "R28") (pin "2") (pinfunction "2_2") (pintype "passive"))
      (node (ref "R33") (pin "2") (pinfunction "2_2") (pintype "passive"))
    )
    (net (code "23") (name "/P_DO_CON15") (class "Default")
      (node (ref "R29") (pin "2") (pinfunction "2_2") (pintype "passive"))
      (node (ref "R34") (pin "2") (pinfunction "2_2") (pintype "passive"))
    )
    (net (code "24") (name "/P_DO_CON16") (class "Default")
      (node (ref "R35") (pin "2") (pinfunction "2_2") (pintype "passive"))
      (node (ref "R40") (pin "2") (pinfunction "2_2") (pintype "passive"))
    )
    (net (code "25") (name "/P_DO_CON17") (class "Default")
      (node (ref "R36") (pin "2") (pinfunction "2_2") (pintype "passive"))
      (node (ref "R41") (pin "2") (pinfunction "2_2") (pintype "passive"))
    )
    (net (code "26") (name "/P_DO_CON18") (class "Default")
      (node (ref "R37") (pin "2") (pinfunction "2_2") (pintype "passive"))
      (node (ref "R42") (pin "2") (pinfunction "2_2") (pintype "passive"))
    )
    (net (code "27") (name "/X_ADC_IN1") (class "Default")
      (node (ref "R22") (pin "1") (pinfunction "1_1") (pintype "passive"))
    )
    (net (code "28") (name "/X_ADC_IN2") (class "Default")
      (node (ref "R44") (pin "1") (pinfunction "1_1") (pintype "passive"))
    )
    (net (code "29") (name "/X_DIN_GND1") (class "Default")
      (node (ref "D21") (pin "2") (pinfunction "K_2") (pintype "passive"))
    )
    (net (code "30") (name "/X_DIN_GND2") (class "Default")
      (node (ref "D22") (pin "2") (pinfunction "K_2") (pintype "passive"))
    )
    (net (code "31") (name "/X_DIN_GND3") (class "Default")
      (node (ref "D23") (pin "2") (pinfunction "K_2") (pintype "passive"))
    )
    (net (code "32") (name "/X_DIN_GND4") (class "Default")
      (node (ref "D25") (pin "2") (pinfunction "K_2") (pintype "passive"))
    )
    (net (code "33") (name "/X_DIN_GND5") (class "Default")
      (node (ref "D26") (pin "2") (pinfunction "K_2") (pintype "passive"))
    )
    (net (code "34") (name "/X_DIN_GND6") (class "Default")
      (node (ref "D27") (pin "2") (pinfunction "K_2") (pintype "passive"))
    )
    (net (code "35") (name "/X_DO1") (class "Default")
      (node (ref "U3") (pin "5") (pinfunction "5_5") (pintype "passive"))
    )
    (net (code "36") (name "/X_DO2") (class "Default")
      (node (ref "U4") (pin "5") (pinfunction "5_5") (pintype "passive"))
    )
    (net (code "37") (name "/X_DO3") (class "Default")
      (node (ref "U5") (pin "5") (pinfunction "5_5") (pintype "passive"))
    )
    (net (code "38") (name "/X_DO4") (class "Default")
      (node (ref "U6") (pin "5") (pinfunction "5_5") (pintype "passive"))
    )
    (net (code "39") (name "/X_DO5") (class "Default")
      (node (ref "U7") (pin "5") (pinfunction "5_5") (pintype "passive"))
    )
    (net (code "40") (name "/X_DO6") (class "Default")
      (node (ref "U8") (pin "5") (pinfunction "5_5") (pintype "passive"))
    )
    (net (code "41") (name "/X_DO7") (class "Default")
      (node (ref "U9") (pin "5") (pinfunction "5_5") (pintype "passive"))
    )
    (net (code "42") (name "/X_DO8") (class "Default")
      (node (ref "U10") (pin "5") (pinfunction "5_5") (pintype "passive"))
    )
    (net (code "43") (name "/X_DO9") (class "Default")
      (node (ref "U11") (pin "5") (pinfunction "5_5") (pintype "passive"))
    )
    (net (code "44") (name "/X_DO10") (class "Default")
      (node (ref "U12") (pin "5") (pinfunction "5_5") (pintype "passive"))
    )
    (net (code "45") (name "/X_DO11") (class "Default")
      (node (ref "U13") (pin "5") (pinfunction "5_5") (pintype "passive"))
    )
    (net (code "46") (name "/X_DO12") (class "Default")
      (node (ref "U14") (pin "5") (pinfunction "5_5") (pintype "passive"))
    )
    (net (code "47") (name "/X_DO13") (class "Default")
      (node (ref "U15") (pin "5") (pinfunction "5_5") (pintype "passive"))
    )
    (net (code "48") (name "/X_DO14") (class "Default")
      (node (ref "U16") (pin "5") (pinfunction "5_5") (pintype "passive"))
    )
    (net (code "49") (name "/X_DO15") (class "Default")
      (node (ref "U17") (pin "5") (pinfunction "5_5") (pintype "passive"))
    )
    (net (code "50") (name "/X_DO16") (class "Default")
      (node (ref "U18") (pin "5") (pinfunction "5_5") (pintype "passive"))
    )
    (net (code "51") (name "/X_DO17") (class "Default")
      (node (ref "U19") (pin "5") (pinfunction "5_5") (pintype "passive"))
    )
    (net (code "52") (name "/X_DO18") (class "Default")
      (node (ref "U20") (pin "5") (pinfunction "5_5") (pintype "passive"))
    )
    (net (code "53") (name "3V3") (class "Default")
      (node (ref "R49") (pin "2") (pinfunction "2_2") (pintype "passive"))
      (node (ref "R51") (pin "2") (pinfunction "2_2") (pintype "passive"))
      (node (ref "R53") (pin "2") (pinfunction "2_2") (pintype "passive"))
      (node (ref "R55") (pin "2") (pinfunction "2_2") (pintype "passive"))
      (node (ref "R57") (pin "2") (pinfunction "2_2") (pintype "passive"))
      (node (ref "R60") (pin "2") (pinfunction "2_2") (pintype "passive"))
    )
    (net (code "54") (name "5V") (class "Default")
      (node (ref "D10") (pin "2") (pinfunction "K_2") (pintype "passive"))
      (node (ref "D11") (pin "2") (pinfunction "K_2") (pintype "passive"))
      (node (ref "D12") (pin "2") (pinfunction "K_2") (pintype "passive"))
      (node (ref "D13") (pin "2") (pinfunction "K_2") (pintype "passive"))
      (node (ref "D14") (pin "2") (pinfunction "K_2") (pintype "passive"))
      (node (ref "D15") (pin "2") (pinfunction "K_2") (pintype "passive"))
      (node (ref "D16") (pin "2") (pinfunction "K_2") (pintype "passive"))
      (node (ref "D17") (pin "2") (pinfunction "K_2") (pintype "passive"))
      (node (ref "D18") (pin "2") (pinfunction "K_2") (pintype "passive"))
      (node (ref "D19") (pin "2") (pinfunction "K_2") (pintype "passive"))
      (node (ref "D20") (pin "2") (pinfunction "K_2") (pintype "passive"))
      (node (ref "D3") (pin "2") (pinfunction "K_2") (pintype "passive"))
      (node (ref "D4") (pin "2") (pinfunction "K_2") (pintype "passive"))
      (node (ref "D5") (pin "2") (pinfunction "K_2") (pintype "passive"))
      (node (ref "D6") (pin "2") (pinfunction "K_2") (pintype "passive"))
      (node (ref "D7") (pin "2") (pinfunction "K_2") (pintype "passive"))
      (node (ref "D8") (pin "2") (pinfunction "K_2") (pintype "passive"))
      (node (ref "D9") (pin "2") (pinfunction "K_2") (pintype "passive"))
      (node (ref "L4") (pin "1") (pinfunction "1_1") (pintype "passive"))
      (node (ref "U10") (pin "9") (pinfunction "9_9") (pintype "passive"))
      (node (ref "U11") (pin "9") (pinfunction "9_9") (pintype "passive"))
      (node (ref "U12") (pin "9") (pinfunction "9_9") (pintype "passive"))
      (node (ref "U13") (pin "9") (pinfunction "9_9") (pintype "passive"))
      (node (ref "U14") (pin "9") (pinfunction "9_9") (pintype "passive"))
      (node (ref "U15") (pin "9") (pinfunction "9_9") (pintype "passive"))
      (node (ref "U16") (pin "9") (pinfunction "9_9") (pintype "passive"))
      (node (ref "U17") (pin "9") (pinfunction "9_9") (pintype "passive"))
      (node (ref "U18") (pin "9") (pinfunction "9_9") (pintype "passive"))
      (node (ref "U19") (pin "9") (pinfunction "9_9") (pintype "passive"))
      (node (ref "U20") (pin "9") (pinfunction "9_9") (pintype "passive"))
      (node (ref "U3") (pin "9") (pinfunction "9_9") (pintype "passive"))
      (node (ref "U4") (pin "9") (pinfunction "9_9") (pintype "passive"))
      (node (ref "U5") (pin "9") (pinfunction "9_9") (pintype "passive"))
      (node (ref "U6") (pin "9") (pinfunction "9_9") (pintype "passive"))
      (node (ref "U7") (pin "9") (pinfunction "9_9") (pintype "passive"))
      (node (ref "U8") (pin "9") (pinfunction "9_9") (pintype "passive"))
      (node (ref "U9") (pin "9") (pinfunction "9_9") (pintype "passive"))
    )
    (net (code "55") (name "5VA") (class "Default")
      (node (ref "C12") (pin "1") (pinfunction "1_1") (pintype "passive"))
      (node (ref "L4") (pin "2") (pinfunction "2_2") (pintype "passive"))
      (node (ref "U21") (pin "8") (pinfunction "+_8") (pintype "passive"))
    )
    (net (code "56") (name "AGND") (class "Default")
      (node (ref "C12") (pin "2") (pinfunction "2_2") (pintype "passive"))
      (node (ref "C13") (pin "1") (pinfunction "1_1") (pintype "passive"))
      (node (ref "C14") (pin "1") (pinfunction "1_1") (pintype "passive"))
      (node (ref "L3") (pin "2") (pinfunction "2_2") (pintype "passive"))
      (node (ref "R43") (pin "1") (pinfunction "1_1") (pintype "passive"))
      (node (ref "R47") (pin "2") (pinfunction "2_2") (pintype "passive"))
      (node (ref "U21") (pin "4") (pinfunction "-_4") (pintype "passive"))
    )
    (net (code "57") (name "GND") (class "Default")
      (node (ref "C15") (pin "2") (pinfunction "2_2") (pintype "passive"))
      (node (ref "C16") (pin "2") (pinfunction "2_2") (pintype "passive"))
      (node (ref "C17") (pin "2") (pinfunction "2_2") (pintype "passive"))
      (node (ref "C18") (pin "2") (pinfunction "2_2") (pintype "passive"))
      (node (ref "C19") (pin "2") (pinfunction "2_2") (pintype "passive"))
      (node (ref "C20") (pin "2") (pinfunction "2_2") (pintype "passive"))
      (node (ref "L3") (pin "1") (pinfunction "1_1") (pintype "passive"))
      (node (ref "Q1") (pin "2") (pinfunction "E_2") (pintype "passive"))
      (node (ref "Q10") (pin "2") (pinfunction "E_2") (pintype "passive"))
      (node (ref "Q11") (pin "2") (pinfunction "E_2") (pintype "passive"))
      (node (ref "Q12") (pin "2") (pinfunction "E_2") (pintype "passive"))
      (node (ref "Q13") (pin "2") (pinfunction "E_2") (pintype "passive"))
      (node (ref "Q14") (pin "2") (pinfunction "E_2") (pintype "passive"))
      (node (ref "Q15") (pin "2") (pinfunction "E_2") (pintype "passive"))
      (node (ref "Q16") (pin "2") (pinfunction "E_2") (pintype "passive"))
      (node (ref "Q17") (pin "2") (pinfunction "E_2") (pintype "passive"))
      (node (ref "Q18") (pin "2") (pinfunction "E_2") (pintype "passive"))
      (node (ref "Q2") (pin "2") (pinfunction "E_2") (pintype "passive"))
      (node (ref "Q3") (pin "2") (pinfunction "E_2") (pintype "passive"))
      (node (ref "Q4") (pin "2") (pinfunction "E_2") (pintype "passive"))
      (node (ref "Q5") (pin "2") (pinfunction "E_2") (pintype "passive"))
      (node (ref "Q6") (pin "2") (pinfunction "E_2") (pintype "passive"))
      (node (ref "Q7") (pin "2") (pinfunction "E_2") (pintype "passive"))
      (node (ref "Q8") (pin "2") (pinfunction "E_2") (pintype "passive"))
      (node (ref "Q9") (pin "2") (pinfunction "E_2") (pintype "passive"))
      (node (ref "R10") (pin "1") (pinfunction "1_1") (pintype "passive"))
      (node (ref "R11") (pin "1") (pinfunction "1_1") (pintype "passive"))
      (node (ref "R12") (pin "1") (pinfunction "1_1") (pintype "passive"))
      (node (ref "R13") (pin "1") (pinfunction "1_1") (pintype "passive"))
      (node (ref "R19") (pin "1") (pinfunction "1_1") (pintype "passive"))
      (node (ref "R20") (pin "1") (pinfunction "1_1") (pintype "passive"))
      (node (ref "R21") (pin "1") (pinfunction "1_1") (pintype "passive"))
      (node (ref "R23") (pin "1") (pinfunction "1_1") (pintype "passive"))
      (node (ref "R24") (pin "1") (pinfunction "1_1") (pintype "passive"))
      (node (ref "R30") (pin "1") (pinfunction "1_1") (pintype "passive"))
      (node (ref "R31") (pin "1") (pinfunction "1_1") (pintype "passive"))
      (node (ref "R32") (pin "1") (pinfunction "1_1") (pintype "passive"))
      (node (ref "R33") (pin "1") (pinfunction "1_1") (pintype "passive"))
      (node (ref "R34") (pin "1") (pinfunction "1_1") (pintype "passive"))
      (node (ref "R40") (pin "1") (pinfunction "1_1") (pintype "passive"))
      (node (ref "R41") (pin "1") (pinfunction "1_1") (pintype "passive"))
      (node (ref "R42") (pin "1") (pinfunction "1_1") (pintype "passive"))
      (node (ref "R9") (pin "1") (pinfunction "1_1") (pintype "passive"))
      (node (ref "U10") (pin "1") (pinfunction "1_1") (pintype "passive"))
      (node (ref "U11") (pin "1") (pinfunction "1_1") (pintype "passive"))
      (node (ref "U12") (pin "1") (pinfunction "1_1") (pintype "passive"))
      (node (ref "U13") (pin "1") (pinfunction "1_1") (pintype "passive"))
      (node (ref "U14") (pin "1") (pinfunction "1_1") (pintype "passive"))
      (node (ref "U15") (pin "1") (pinfunction "1_1") (pintype "passive"))
      (node (ref "U16") (pin "1") (pinfunction "1_1") (pintype "passive"))
      (node (ref "U17") (pin "1") (pinfunction "1_1") (pintype "passive"))
      (node (ref "U18") (pin "1") (pinfunction "1_1") (pintype "passive"))
      (node (ref "U19") (pin "1") (pinfunction "1_1") (pintype "passive"))
      (node (ref "U20") (pin "1") (pinfunction "1_1") (pintype "passive"))
      (node (ref "U22") (pin "3") (pinfunction "E_3") (pintype "passive"))
      (node (ref "U23") (pin "3") (pinfunction "E_3") (pintype "passive"))
      (node (ref "U24") (pin "3") (pinfunction "E_3") (pintype "passive"))
      (node (ref "U25") (pin "3") (pinfunction "E_3") (pintype "passive"))
      (node (ref "U26") (pin "3") (pinfunction "E_3") (pintype "passive"))
      (node (ref "U3") (pin "1") (pinfunction "1_1") (pintype "passive"))
      (node (ref "U30") (pin "3") (pinfunction "E_3") (pintype "passive"))
      (node (ref "U4") (pin "1") (pinfunction "1_1") (pintype "passive"))
      (node (ref "U5") (pin "1") (pinfunction "1_1") (pintype "passive"))
      (node (ref "U6") (pin "1") (pinfunction "1_1") (pintype "passive"))
      (node (ref "U7") (pin "1") (pinfunction "1_1") (pintype "passive"))
      (node (ref "U8") (pin "1") (pinfunction "1_1") (pintype "passive"))
      (node (ref "U9") (pin "1") (pinfunction "1_1") (pintype "passive"))
    )
    (net (code "58") (name "Net-(C13-Pad2)") (class "Default")
      (node (ref "C13") (pin "2") (pinfunction "2_2") (pintype "passive"))
      (node (ref "R38") (pin "1") (pinfunction "1_1") (pintype "passive"))
      (node (ref "U21") (pin "3") (pintype "passive"))
    )
    (net (code "59") (name "Net-(C14-Pad2)") (class "Default")
      (node (ref "C14") (pin "2") (pinfunction "2_2") (pintype "passive"))
      (node (ref "R45") (pin "1") (pinfunction "1_1") (pintype "passive"))
      (node (ref "U21") (pin "5") (pintype "passive"))
    )
    (net (code "60") (name "Net-(D3-A)") (class "Default")
      (node (ref "D3") (pin "1") (pinfunction "A_1") (pintype "passive"))
      (node (ref "Q1") (pin "3") (pinfunction "C_3") (pintype "passive"))
      (node (ref "U3") (pin "2") (pinfunction "2_2") (pintype "passive"))
    )
    (net (code "61") (name "Net-(D4-A)") (class "Default")
      (node (ref "D4") (pin "1") (pinfunction "A_1") (pintype "passive"))
      (node (ref "Q2") (pin "3") (pinfunction "C_3") (pintype "passive"))
      (node (ref "U4") (pin "2") (pinfunction "2_2") (pintype "passive"))
    )
    (net (code "62") (name "Net-(D5-A)") (class "Default")
      (node (ref "D5") (pin "1") (pinfunction "A_1") (pintype "passive"))
      (node (ref "Q3") (pin "3") (pinfunction "C_3") (pintype "passive"))
      (node (ref "U5") (pin "2") (pinfunction "2_2") (pintype "passive"))
    )
    (net (code "63") (name "Net-(D6-A)") (class "Default")
      (node (ref "D6") (pin "1") (pinfunction "A_1") (pintype "passive"))
      (node (ref "Q4") (pin "3") (pinfunction "C_3") (pintype "passive"))
      (node (ref "U6") (pin "2") (pinfunction "2_2") (pintype "passive"))
    )
    (net (code "64") (name "Net-(D7-A)") (class "Default")
      (node (ref "D7") (pin "1") (pinfunction "A_1") (pintype "passive"))
      (node (ref "Q5") (pin "3") (pinfunction "C_3") (pintype "passive"))
      (node (ref "U7") (pin "2") (pinfunction "2_2") (pintype "passive"))
    )
    (net (code "65") (name "Net-(D8-A)") (class "Default")
      (node (ref "D8") (pin "1") (pinfunction "A_1") (pintype "passive"))
      (node (ref "Q6") (pin "3") (pinfunction "C_3") (pintype "passive"))
      (node (ref "U8") (pin "2") (pinfunction "2_2") (pintype "passive"))
    )
    (net (code "66") (name "Net-(D9-A)") (class "Default")
      (node (ref "D9") (pin "1") (pinfunction "A_1") (pintype "passive"))
      (node (ref "Q7") (pin "3") (pinfunction "C_3") (pintype "passive"))
      (node (ref "U9") (pin "2") (pinfunction "2_2") (pintype "passive"))
    )
    (net (code "67") (name "Net-(D10-A)") (class "Default")
      (node (ref "D10") (pin "1") (pinfunction "A_1") (pintype "passive"))
      (node (ref "Q8") (pin "3") (pinfunction "C_3") (pintype "passive"))
      (node (ref "U10") (pin "2") (pinfunction "2_2") (pintype "passive"))
    )
    (net (code "68") (name "Net-(D11-A)") (class "Default")
      (node (ref "D11") (pin "1") (pinfunction "A_1") (pintype "passive"))
      (node (ref "Q9") (pin "3") (pinfunction "C_3") (pintype "passive"))
      (node (ref "U11") (pin "2") (pinfunction "2_2") (pintype "passive"))
    )
    (net (code "69") (name "Net-(D12-A)") (class "Default")
      (node (ref "D12") (pin "1") (pinfunction "A_1") (pintype "passive"))
      (node (ref "Q10") (pin "3") (pinfunction "C_3") (pintype "passive"))
      (node (ref "U12") (pin "2") (pinfunction "2_2") (pintype "passive"))
    )
    (net (code "70") (name "Net-(D13-A)") (class "Default")
      (node (ref "D13") (pin "1") (pinfunction "A_1") (pintype "passive"))
      (node (ref "Q11") (pin "3") (pinfunction "C_3") (pintype "passive"))
      (node (ref "U13") (pin "2") (pinfunction "2_2") (pintype "passive"))
    )
    (net (code "71") (name "Net-(D14-A)") (class "Default")
      (node (ref "D14") (pin "1") (pinfunction "A_1") (pintype "passive"))
      (node (ref "Q12") (pin "3") (pinfunction "C_3") (pintype "passive"))
      (node (ref "U14") (pin "2") (pinfunction "2_2") (pintype "passive"))
    )
    (net (code "72") (name "Net-(D15-A)") (class "Default")
      (node (ref "D15") (pin "1") (pinfunction "A_1") (pintype "passive"))
      (node (ref "Q13") (pin "3") (pinfunction "C_3") (pintype "passive"))
      (node (ref "U15") (pin "2") (pinfunction "2_2") (pintype "passive"))
    )
    (net (code "73") (name "Net-(D16-A)") (class "Default")
      (node (ref "D16") (pin "1") (pinfunction "A_1") (pintype "passive"))
      (node (ref "Q14") (pin "3") (pinfunction "C_3") (pintype "passive"))
      (node (ref "U16") (pin "2") (pinfunction "2_2") (pintype "passive"))
    )
    (net (code "74") (name "Net-(D17-A)") (class "Default")
      (node (ref "D17") (pin "1") (pinfunction "A_1") (pintype "passive"))
      (node (ref "Q15") (pin "3") (pinfunction "C_3") (pintype "passive"))
      (node (ref "U17") (pin "2") (pinfunction "2_2") (pintype "passive"))
    )
    (net (code "75") (name "Net-(D18-A)") (class "Default")
      (node (ref "D18") (pin "1") (pinfunction "A_1") (pintype "passive"))
      (node (ref "Q16") (pin "3") (pinfunction "C_3") (pintype "passive"))
      (node (ref "U18") (pin "2") (pinfunction "2_2") (pintype "passive"))
    )
    (net (code "76") (name "Net-(D19-A)") (class "Default")
      (node (ref "D19") (pin "1") (pinfunction "A_1") (pintype "passive"))
      (node (ref "Q17") (pin "3") (pinfunction "C_3") (pintype "passive"))
      (node (ref "U19") (pin "2") (pinfunction "2_2") (pintype "passive"))
    )
    (net (code "77") (name "Net-(D20-A)") (class "Default")
      (node (ref "D20") (pin "1") (pinfunction "A_1") (pintype "passive"))
      (node (ref "Q18") (pin "3") (pinfunction "C_3") (pintype "passive"))
      (node (ref "U20") (pin "2") (pinfunction "2_2") (pintype "passive"))
    )
    (net (code "78") (name "Net-(D21-A)") (class "Default")
      (node (ref "D21") (pin "1") (pinfunction "A_1") (pintype "passive"))
      (node (ref "U22") (pin "2") (pinfunction "K_2") (pintype "passive"))
    )
    (net (code "79") (name "Net-(D22-A)") (class "Default")
      (node (ref "D22") (pin "1") (pinfunction "A_1") (pintype "passive"))
      (node (ref "U23") (pin "2") (pinfunction "K_2") (pintype "passive"))
    )
    (net (code "80") (name "Net-(D23-A)") (class "Default")
      (node (ref "D23") (pin "1") (pinfunction "A_1") (pintype "passive"))
      (node (ref "U24") (pin "2") (pinfunction "K_2") (pintype "passive"))
    )
    (net (code "81") (name "Net-(D25-A)") (class "Default")
      (node (ref "D25") (pin "1") (pinfunction "A_1") (pintype "passive"))
      (node (ref "U25") (pin "2") (pinfunction "K_2") (pintype "passive"))
    )
    (net (code "82") (name "Net-(D26-A)") (class "Default")
      (node (ref "D26") (pin "1") (pinfunction "A_1") (pintype "passive"))
      (node (ref "U26") (pin "2") (pinfunction "K_2") (pintype "passive"))
    )
    (net (code "83") (name "Net-(D27-A)") (class "Default")
      (node (ref "D27") (pin "1") (pinfunction "A_1") (pintype "passive"))
      (node (ref "U30") (pin "2") (pinfunction "K_2") (pintype "passive"))
    )
    (net (code "84") (name "Net-(Q1-B)") (class "Default")
      (node (ref "Q1") (pin "1") (pinfunction "B_1") (pintype "passive"))
      (node (ref "R4") (pin "1") (pinfunction "1_1") (pintype "passive"))
    )
    (net (code "85") (name "Net-(Q2-B)") (class "Default")
      (node (ref "Q2") (pin "1") (pinfunction "B_1") (pintype "passive"))
      (node (ref "R5") (pin "1") (pinfunction "1_1") (pintype "passive"))
    )
    (net (code "86") (name "Net-(Q3-B)") (class "Default")
      (node (ref "Q3") (pin "1") (pinfunction "B_1") (pintype "passive"))
      (node (ref "R6") (pin "1") (pinfunction "1_1") (pintype "passive"))
    )
    (net (code "87") (name "Net-(Q4-B)") (class "Default")
      (node (ref "Q4") (pin "1") (pinfunction "B_1") (pintype "passive"))
      (node (ref "R7") (pin "1") (pinfunction "1_1") (pintype "passive"))
    )
    (net (code "88") (name "Net-(Q5-B)") (class "Default")
      (node (ref "Q5") (pin "1") (pinfunction "B_1") (pintype "passive"))
      (node (ref "R8") (pin "1") (pinfunction "1_1") (pintype "passive"))
    )
    (net (code "89") (name "Net-(Q6-B)") (class "Default")
      (node (ref "Q6") (pin "1") (pinfunction "B_1") (pintype "passive"))
      (node (ref "R14") (pin "1") (pinfunction "1_1") (pintype "passive"))
    )
    (net (code "90") (name "Net-(Q7-B)") (class "Default")
      (node (ref "Q7") (pin "1") (pinfunction "B_1") (pintype "passive"))
      (node (ref "R15") (pin "1") (pinfunction "1_1") (pintype "passive"))
    )
    (net (code "91") (name "Net-(Q8-B)") (class "Default")
      (node (ref "Q8") (pin "1") (pinfunction "B_1") (pintype "passive"))
      (node (ref "R16") (pin "1") (pinfunction "1_1") (pintype "passive"))
    )
    (net (code "92") (name "Net-(Q9-B)") (class "Default")
      (node (ref "Q9") (pin "1") (pinfunction "B_1") (pintype "passive"))
      (node (ref "R17") (pin "1") (pinfunction "1_1") (pintype "passive"))
    )
    (net (code "93") (name "Net-(Q10-B)") (class "Default")
      (node (ref "Q10") (pin "1") (pinfunction "B_1") (pintype "passive"))
      (node (ref "R18") (pin "1") (pinfunction "1_1") (pintype "passive"))
    )
    (net (code "94") (name "Net-(Q11-B)") (class "Default")
      (node (ref "Q11") (pin "1") (pinfunction "B_1") (pintype "passive"))
      (node (ref "R25") (pin "1") (pinfunction "1_1") (pintype "passive"))
    )
    (net (code "95") (name "Net-(Q12-B)") (class "Default")
      (node (ref "Q12") (pin "1") (pinfunction "B_1") (pintype "passive"))
      (node (ref "R26") (pin "1") (pinfunction "1_1") (pintype "passive"))
    )
    (net (code "96") (name "Net-(Q13-B)") (class "Default")
      (node (ref "Q13") (pin "1") (pinfunction "B_1") (pintype "passive"))
      (node (ref "R27") (pin "1") (pinfunction "1_1") (pintype "passive"))
    )
    (net (code "97") (name "Net-(Q14-B)") (class "Default")
      (node (ref "Q14") (pin "1") (pinfunction "B_1") (pintype "passive"))
      (node (ref "R28") (pin "1") (pinfunction "1_1") (pintype "passive"))
    )
    (net (code "98") (name "Net-(Q15-B)") (class "Default")
      (node (ref "Q15") (pin "1") (pinfunction "B_1") (pintype "passive"))
      (node (ref "R29") (pin "1") (pinfunction "1_1") (pintype "passive"))
    )
    (net (code "99") (name "Net-(Q16-B)") (class "Default")
      (node (ref "Q16") (pin "1") (pinfunction "B_1") (pintype "passive"))
      (node (ref "R35") (pin "1") (pinfunction "1_1") (pintype "passive"))
    )
    (net (code "100") (name "Net-(Q17-B)") (class "Default")
      (node (ref "Q17") (pin "1") (pinfunction "B_1") (pintype "passive"))
      (node (ref "R36") (pin "1") (pinfunction "1_1") (pintype "passive"))
    )
    (net (code "101") (name "Net-(Q18-B)") (class "Default")
      (node (ref "Q18") (pin "1") (pinfunction "B_1") (pintype "passive"))
      (node (ref "R37") (pin "1") (pinfunction "1_1") (pintype "passive"))
    )
    (net (code "102") (name "Net-(R22-Pad2)") (class "Default")
      (node (ref "R22") (pin "2") (pinfunction "2_2") (pintype "passive"))
      (node (ref "R38") (pin "2") (pinfunction "2_2") (pintype "passive"))
      (node (ref "R43") (pin "2") (pinfunction "2_2") (pintype "passive"))
    )
    (net (code "103") (name "Net-(R44-Pad2)") (class "Default")
      (node (ref "R44") (pin "2") (pinfunction "2_2") (pintype "passive"))
      (node (ref "R45") (pin "2") (pinfunction "2_2") (pintype "passive"))
      (node (ref "R47") (pin "1") (pinfunction "1_1") (pintype "passive"))
    )
    (net (code "104") (name "Net-(U21A-out)") (class "Default")
      (node (ref "R39") (pin "2") (pinfunction "2_2") (pintype "passive"))
      (node (ref "U21") (pin "1") (pinfunction "out_1") (pintype "passive"))
      (node (ref "U21") (pin "2") (pintype "passive"))
    )
    (net (code "105") (name "Net-(U21B-out)") (class "Default")
      (node (ref "R46") (pin "2") (pinfunction "2_2") (pintype "passive"))
      (node (ref "U21") (pin "6") (pintype "passive"))
      (node (ref "U21") (pin "7") (pinfunction "out_7") (pintype "passive"))
    )
    (net (code "106") (name "Net-(U22-A)") (class "Default")
      (node (ref "R48") (pin "2") (pinfunction "2_2") (pintype "passive"))
      (node (ref "U22") (pin "1") (pinfunction "A_1") (pintype "passive"))
    )
    (net (code "107") (name "Net-(U23-A)") (class "Default")
      (node (ref "R50") (pin "2") (pinfunction "2_2") (pintype "passive"))
      (node (ref "U23") (pin "1") (pinfunction "A_1") (pintype "passive"))
    )
    (net (code "108") (name "Net-(U24-A)") (class "Default")
      (node (ref "R52") (pin "2") (pinfunction "2_2") (pintype "passive"))
      (node (ref "U24") (pin "1") (pinfunction "A_1") (pintype "passive"))
    )
    (net (code "109") (name "Net-(U25-A)") (class "Default")
      (node (ref "R54") (pin "2") (pinfunction "2_2") (pintype "passive"))
      (node (ref "U25") (pin "1") (pinfunction "A_1") (pintype "passive"))
    )
    (net (code "110") (name "Net-(U26-A)") (class "Default")
      (node (ref "R56") (pin "2") (pinfunction "2_2") (pintype "passive"))
      (node (ref "U26") (pin "1") (pinfunction "A_1") (pintype "passive"))
    )
    (net (code "111") (name "Net-(U30-A)") (class "Default")
      (node (ref "R58") (pin "2") (pinfunction "2_2") (pintype "passive"))
      (node (ref "U30") (pin "1") (pinfunction "A_1") (pintype "passive"))
    )
    (net (code "112") (name "X_VIN") (class "Default")
      (node (ref "R48") (pin "1") (pinfunction "1_1") (pintype "passive"))
      (node (ref "R50") (pin "1") (pinfunction "1_1") (pintype "passive"))
      (node (ref "R52") (pin "1") (pinfunction "1_1") (pintype "passive"))
      (node (ref "R54") (pin "1") (pinfunction "1_1") (pintype "passive"))
      (node (ref "R56") (pin "1") (pinfunction "1_1") (pintype "passive"))
      (node (ref "R58") (pin "1") (pinfunction "1_1") (pintype "passive"))
      (node (ref "U10") (pin "10") (pinfunction "10_10") (pintype "passive"))
      (node (ref "U11") (pin "10") (pinfunction "10_10") (pintype "passive"))
      (node (ref "U12") (pin "10") (pinfunction "10_10") (pintype "passive"))
      (node (ref "U13") (pin "10") (pinfunction "10_10") (pintype "passive"))
      (node (ref "U14") (pin "10") (pinfunction "10_10") (pintype "passive"))
      (node (ref "U15") (pin "10") (pinfunction "10_10") (pintype "passive"))
      (node (ref "U16") (pin "10") (pinfunction "10_10") (pintype "passive"))
      (node (ref "U17") (pin "10") (pinfunction "10_10") (pintype "passive"))
      (node (ref "U18") (pin "10") (pinfunction "10_10") (pintype "passive"))
      (node (ref "U19") (pin "10") (pinfunction "10_10") (pintype "passive"))
      (node (ref "U20") (pin "10") (pinfunction "10_10") (pintype "passive"))
      (node (ref "U3") (pin "10") (pinfunction "10_10") (pintype "passive"))
      (node (ref "U4") (pin "10") (pinfunction "10_10") (pintype "passive"))
      (node (ref "U5") (pin "10") (pinfunction "10_10") (pintype "passive"))
      (node (ref "U6") (pin "10") (pinfunction "10_10") (pintype "passive"))
      (node (ref "U7") (pin "10") (pinfunction "10_10") (pintype "passive"))
      (node (ref "U8") (pin "10") (pinfunction "10_10") (pintype "passive"))
      (node (ref "U9") (pin "10") (pinfunction "10_10") (pintype "passive"))
    )
    (net (code "113") (name "unconnected-(U3-Pad6)") (class "Default")
      (node (ref "U3") (pin "6") (pinfunction "6_6") (pintype "passive+no_connect"))
    )
    (net (code "114") (name "unconnected-(U4-Pad6)") (class "Default")
      (node (ref "U4") (pin "6") (pinfunction "6_6") (pintype "passive+no_connect"))
    )
    (net (code "115") (name "unconnected-(U5-Pad6)") (class "Default")
      (node (ref "U5") (pin "6") (pinfunction "6_6") (pintype "passive+no_connect"))
    )
    (net (code "116") (name "unconnected-(U6-Pad6)") (class "Default")
      (node (ref "U6") (pin "6") (pinfunction "6_6") (pintype "passive+no_connect"))
    )
    (net (code "117") (name "unconnected-(U7-Pad6)") (class "Default")
      (node (ref "U7") (pin "6") (pinfunction "6_6") (pintype "passive+no_connect"))
    )
    (net (code "118") (name "unconnected-(U8-Pad6)") (class "Default")
      (node (ref "U8") (pin "6") (pinfunction "6_6") (pintype "passive+no_connect"))
    )
    (net (code "119") (name "unconnected-(U9-Pad6)") (class "Default")
      (node (ref "U9") (pin "6") (pinfunction "6_6") (pintype "passive+no_connect"))
    )
    (net (code "120") (name "unconnected-(U10-Pad6)") (class "Default")
      (node (ref "U10") (pin "6") (pinfunction "6_6") (pintype "passive+no_connect"))
    )
    (net (code "121") (name "unconnected-(U11-Pad6)") (class "Default")
      (node (ref "U11") (pin "6") (pinfunction "6_6") (pintype "passive+no_connect"))
    )
    (net (code "122") (name "unconnected-(U12-Pad6)") (class "Default")
      (node (ref "U12") (pin "6") (pinfunction "6_6") (pintype "passive+no_connect"))
    )
    (net (code "123") (name "unconnected-(U13-Pad6)") (class "Default")
      (node (ref "U13") (pin "6") (pinfunction "6_6") (pintype "passive+no_connect"))
    )
    (net (code "124") (name "unconnected-(U14-Pad6)") (class "Default")
      (node (ref "U14") (pin "6") (pinfunction "6_6") (pintype "passive+no_connect"))
    )
    (net (code "125") (name "unconnected-(U15-Pad6)") (class "Default")
      (node (ref "U15") (pin "6") (pinfunction "6_6") (pintype "passive+no_connect"))
    )
    (net (code "126") (name "unconnected-(U16-Pad6)") (class "Default")
      (node (ref "U16") (pin "6") (pinfunction "6_6") (pintype "passive+no_connect"))
    )
    (net (code "127") (name "unconnected-(U17-Pad6)") (class "Default")
      (node (ref "U17") (pin "6") (pinfunction "6_6") (pintype "passive+no_connect"))
    )
    (net (code "128") (name "unconnected-(U18-Pad6)") (class "Default")
      (node (ref "U18") (pin "6") (pinfunction "6_6") (pintype "passive+no_connect"))
    )
    (net (code "129") (name "unconnected-(U19-Pad6)") (class "Default")
      (node (ref "U19") (pin "6") (pinfunction "6_6") (pintype "passive+no_connect"))
    )
    (net (code "130") (name "unconnected-(U20-Pad6)") (class "Default")
      (node (ref "U20") (pin "6") (pinfunction "6_6") (pintype "passive+no_connect"))
    )
  )
)
